# TPSM82822_2A_Buck_Module.net
KiCad netlist of a schematic drawn in Altium Designer
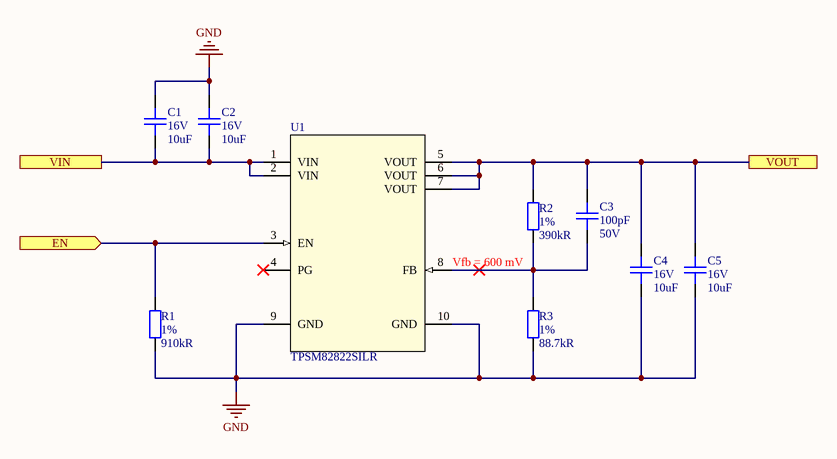
[diagram p0: TPSM82822_2A_Buck_Module.SchDoc]

(export (version "E")
  (design (tool "Eeschema 10.0.6"))
  (components
    (comp (ref "C1")
      (value "CAP CER 10UF 16V X5R 0603")
      (footprint "C0603")
      (description "10µF ±10% 16V Ceramic Capacitor X5R 0603 (1608 Metric)")
      (fields
        (field (name "MANUFACTURER") "Murata")
        (field (name "MANUFACTURER PART NUMBER") "GRM188R61C106KAALJ")
        (field (name "VOLTAGE RATING") "16V")
        (field (name "CAPACITANCE") "10uF")
      )
      (libsource (lib "Control_Board_Model") (part "CAP CER 10UF 16V X5R 0603"))
    )
    (comp (ref "C2")
      (value "CAP CER 10UF 16V X5R 0603")
      (footprint "C0603")
      (description "10µF ±10% 16V Ceramic Capacitor X5R 0603 (1608 Metric)")
      (fields
        (field (name "MANUFACTURER") "Murata")
        (field (name "MANUFACTURER PART NUMBER") "GRM188R61C106KAALJ")
        (field (name "VOLTAGE RATING") "16V")
        (field (name "CAPACITANCE") "10uF")
      )
      (libsource (lib "Control_Board_Model") (part "CAP CER 10UF 16V X5R 0603"))
    )
    (comp (ref "C3")
      (value "CAP CER 100PF 50V C0G/NPO 0402")
      (footprint "C0402")
      (description "100pF ±5% 50V Ceramic Capacitor C0G, NP0 0402 (1005 Metric)")
      (fields
        (field (name "MANUFACTURER") "Yageo")
        (field (name "MANUFACTURER PART NUMBER") "CC0402JRNPO9BN101")
        (field (name "CAPACITANCE") "100pF")
        (field (name "VOLTAGE") "50V")
      )
      (libsource (lib "Control_Board_Model") (part "CAP CER 100PF 50V C0G/NPO 0402"))
    )
    (comp (ref "C4")
      (value "CAP CER 10UF 16V X5R 0603")
      (footprint "C0603")
      (description "10µF ±10% 16V Ceramic Capacitor X5R 0603 (1608 Metric)")
      (fields
        (field (name "MANUFACTURER") "Murata")
        (field (name "MANUFACTURER PART NUMBER") "GRM188R61C106KAALJ")
        (field (name "VOLTAGE RATING") "16V")
        (field (name "CAPACITANCE") "10uF")
      )
      (libsource (lib "Control_Board_Model") (part "CAP CER 10UF 16V X5R 0603"))
    )
    (comp (ref "C5")
      (value "CAP CER 10UF 16V X5R 0603")
      (footprint "C0603")
      (description "10µF ±10% 16V Ceramic Capacitor X5R 0603 (1608 Metric)")
      (fields
        (field (name "MANUFACTURER") "Murata")
        (field (name "MANUFACTURER PART NUMBER") "GRM188R61C106KAALJ")
        (field (name "VOLTAGE RATING") "16V")
        (field (name "CAPACITANCE") "10uF")
      )
      (libsource (lib "Control_Board_Model") (part "CAP CER 10UF 16V X5R 0603"))
    )
    (comp (ref "R1")
      (value "RES SMD 910K OHM 1% 1/16W 0402")
      (footprint "R0402")
      (description "910 kOhms ±1% 0.063W, 1/16W Chip Resistor 0402 (1005 Metric) Moisture Resistant Thick Film")
      (fields
        (field (name "MANUFACTURER") "Yageo")
        (field (name "MANUFACTURER PART NUMBER") "RC0402FR-07910KL")
        (field (name "TOLERANCE") "1%")
        (field (name "RESISTANCE") "910kR")
      )
      (libsource (lib "Control_Board_Model") (part "RES SMD 910K OHM 1% 1/16W 0402"))
    )
    (comp (ref "R2")
      (value "RES SMD 390K OHM 1% 1/16W 0402")
      (footprint "R0402")
      (description "390 kOhms ±1% 0.063W, 1/16W Chip Resistor 0402 (1005 Metric) Moisture Resistant Thick Film")
      (fields
        (field (name "TOLERANCE") "1%")
        (field (name "RESISTANCE") "390kR")
        (field (name "MANUFACTURER") "Yageo")
        (field (name "MANUFACTURER PART NUMBER") "RC0402FR-07390KL")
      )
      (libsource (lib "resistors_smd") (part "RES SMD 390K OHM 1% 1/16W 0402"))
    )
    (comp (ref "R3")
      (value "RES SMD 88.7K OHM 1% 1/16W 0402")
      (footprint "R0402")
      (description "88.7 kOhms ±1% 0.063W, 1/16W Chip Resistor 0402 (1005 Metric) Moisture Resistant Thick Film")
      (fields
        (field (name "MANUFACTURER") "Yageo")
        (field (name "MANUFACTURER PART NUMBER") "RC0402FR-0788K7L")
        (field (name "TOLERANCE") "1%")
        (field (name "RESISTANCE") "88.7kR")
      )
      (libsource (lib "Control_Board_Model") (part "RES SMD 88.7K OHM 1% 1/16W 0402"))
    )
    (comp (ref "U1")
      (value "TPSM82822SILR")
      (footprint "SIL0010D")
      (description "Non-Isolated PoL Module DC DC Converter 1 Output 0.6 ~ 4V    2A 2.4V - 5.5V Input")
      (fields (field (name "MANUFACTURER") "Texas Instruments"))
      (libsource (lib "dcdc_converters") (part "IC TPSM82822SIL 5.5-V INPUT, 2-A STEP-DOWN MODUL"))
    )
  )
  (nets
    (net (code "1") (name "/EN") (class "Default")
      (node (ref "R1") (pin "1") (pinfunction "1_1") (pintype "passive"))
      (node (ref "U1") (pin "3") (pinfunction "EN_3") (pintype "input"))
    )
    (net (code "2") (name "/VIN") (class "Default")
      (node (ref "C1") (pin "1") (pinfunction "1_1") (pintype "passive"))
      (node (ref "C2") (pin "1") (pinfunction "1_1") (pintype "passive"))
      (node (ref "U1") (pin "1") (pinfunction "VIN_1") (pintype "power_in"))
      (node (ref "U1") (pin "2") (pinfunction "VIN_2") (pintype "power_in"))
    )
    (net (code "3") (name "/VOUT") (class "Default")
      (node (ref "C3") (pin "2") (pinfunction "2_2") (pintype "passive"))
      (node (ref "C4") (pin "2") (pinfunction "2_2") (pintype "passive"))
      (node (ref "C5") (pin "2") (pinfunction "2_2") (pintype "passive"))
      (node (ref "R2") (pin "2") (pinfunction "2_2") (pintype "passive"))
      (node (ref "U1") (pin "5") (pinfunction "VOUT_5") (pintype "power_in"))
      (node (ref "U1") (pin "6") (pinfunction "VOUT_6") (pintype "power_in"))
      (node (ref "U1") (pin "7") (pinfunction "VOUT_7") (pintype "power_in"))
    )
    (net (code "4") (name "GND") (class "Default")
      (node (ref "C1") (pin "2") (pinfunction "2_2") (pintype "passive"))
      (node (ref "C2") (pin "2") (pinfunction "2_2") (pintype "passive"))
      (node (ref "C4") (pin "1") (pinfunction "1_1") (pintype "passive"))
      (node (ref "C5") (pin "1") (pinfunction "1_1") (pintype "passive"))
      (node (ref "R1") (pin "2") (pinfunction "2_2") (pintype "passive"))
      (node (ref "R3") (pin "2") (pinfunction "2_2") (pintype "passive"))
      (node (ref "U1") (pin "10") (pinfunction "GND_10") (pintype "power_in"))
      (node (ref "U1") (pin "9") (pinfunction "GND_9") (pintype "power_in"))
    )
    (net (code "5") (name "Net-(U1-FB)") (class "Default")
      (node (ref "C3") (pin "1") (pinfunction "1_1") (pintype "passive"))
      (node (ref "R2") (pin "1") (pinfunction "1_1") (pintype "passive"))
      (node (ref "R3") (pin "1") (pinfunction "1_1") (pintype "passive"))
      (node (ref "U1") (pin "8") (pinfunction "FB_8") (pintype "input"))
    )
    (net (code "6") (name "unconnected-(U1-PG-Pad4)") (class "Default")
      (node (ref "U1") (pin "4") (pinfunction "PG_4") (pintype "open_collector+no_connect"))
    )
  )
)
